# Atmega.net
KiCad netlist of a schematic drawn in EAGLE
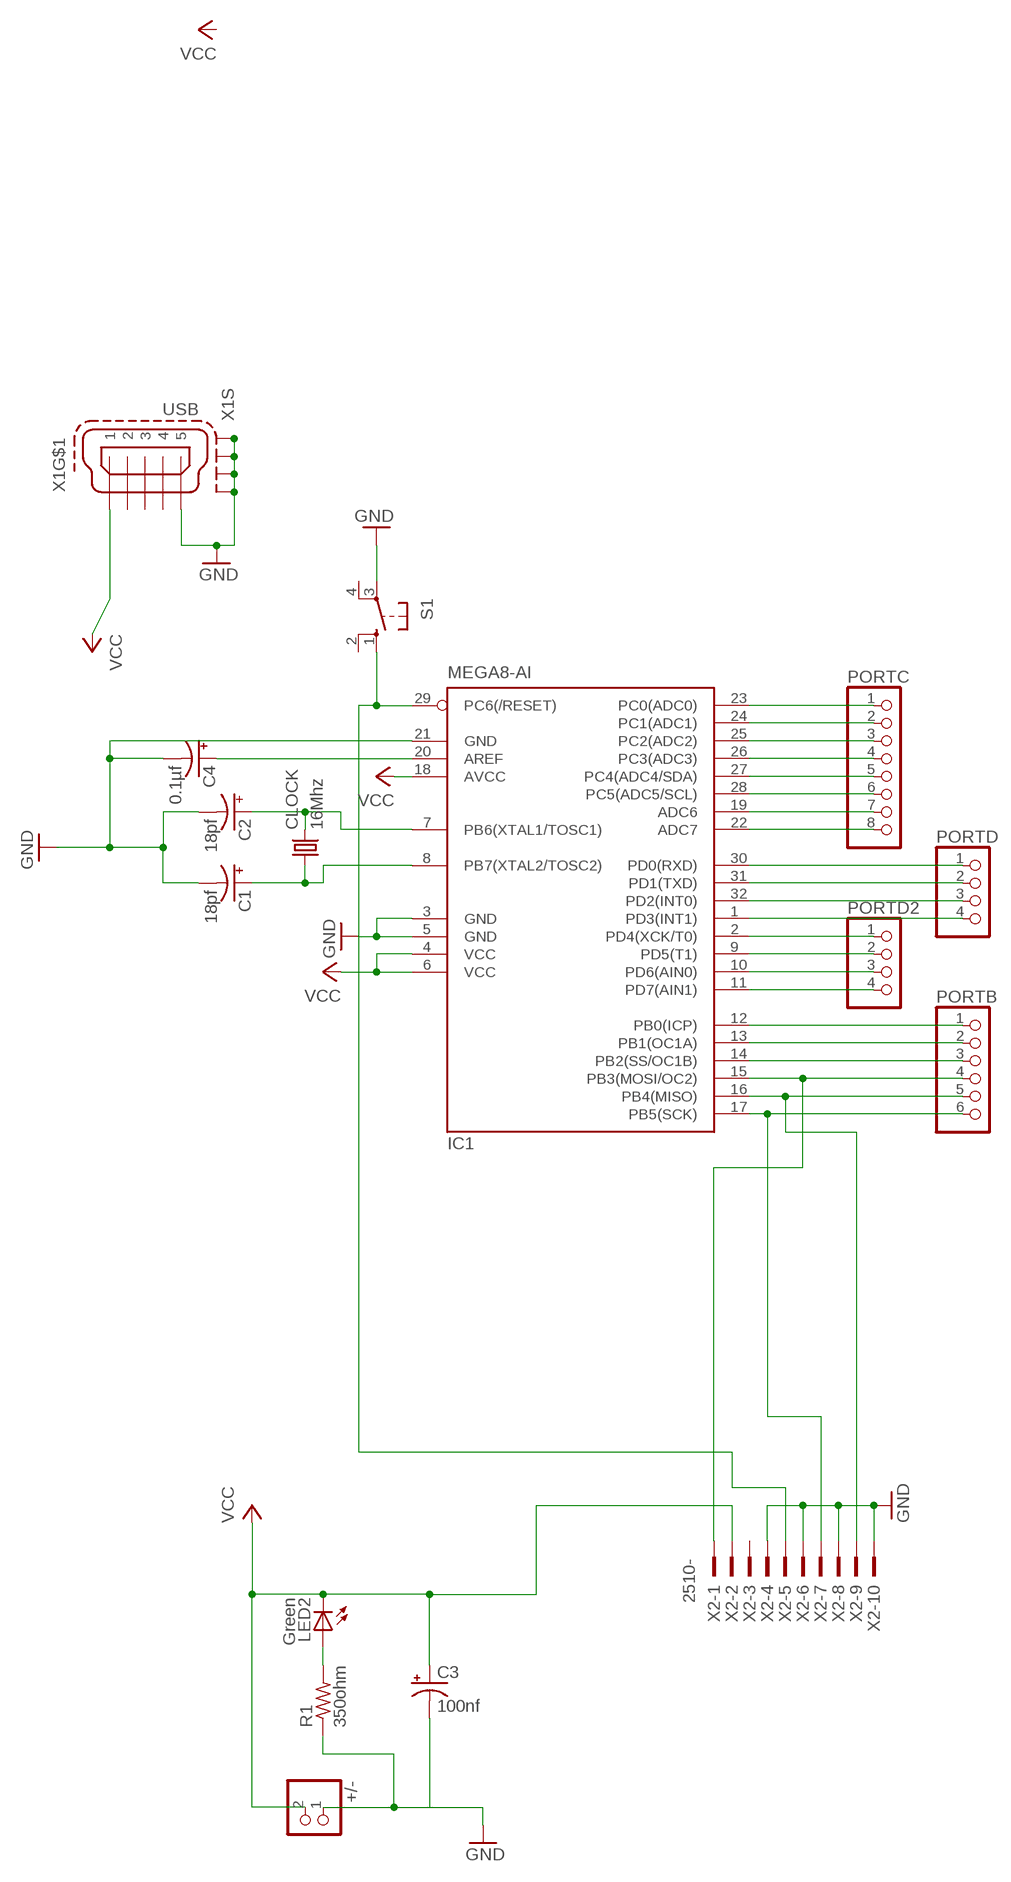
[diagram p0: schematic, sheet 1]

(export (version "E")
  (design (tool "Eeschema 10.0.6"))
  (components
    (comp (ref "+/-")
      (value "PINHD-1X2")
      (footprint "eagle-import:1X02")
      (libsource (lib "eagle-import") (part "PINHD-1X2"))
    )
    (comp (ref "C1")
      (value "18pf")
      (footprint "eagle-import:SMC_Z")
      (libsource (lib "eagle-import") (part "CPOL-USSMCZ"))
    )
    (comp (ref "C2")
      (value "18pf")
      (footprint "eagle-import:SMC_Z")
      (libsource (lib "eagle-import") (part "CPOL-USSMCZ"))
    )
    (comp (ref "C3")
      (value "100nf")
      (footprint "eagle-import:SMC_Z")
      (libsource (lib "eagle-import") (part "CPOL-USSMCZ"))
    )
    (comp (ref "C4")
      (value "0.1µf")
      (footprint "eagle-import:SMC_Z")
      (libsource (lib "eagle-import") (part "CPOL-USSMCZ"))
    )
    (comp (ref "CLOCK")
      (value "16Mhz")
      (footprint "eagle-import:HC49UP")
      (libsource (lib "eagle-import") (part "CRYSTALHC49UP"))
    )
    (comp (ref "IC1")
      (value "MEGA8-AI")
      (footprint "eagle-import:TQFP32-08")
      (fields (field (name "MPN") "ATMEGA8-16AU"))
      (libsource (lib "eagle-import") (part "MEGA8-AI"))
    )
    (comp (ref "LED2")
      (value "Green")
      (footprint "eagle-import:PLCC2")
      (fields (field (name "COLOR") "green"))
      (libsource (lib "eagle-import") (part "_T679-?-1E1F1LG"))
    )
    (comp (ref "PORTB")
      (value "PINHD-1X6")
      (footprint "eagle-import:1X06")
      (libsource (lib "eagle-import") (part "PINHD-1X6"))
    )
    (comp (ref "PORTC")
      (value "PINHD-1X8")
      (footprint "eagle-import:1X08")
      (libsource (lib "eagle-import") (part "PINHD-1X8"))
    )
    (comp (ref "PORTD")
      (value "PINHD-1X4")
      (footprint "eagle-import:1X04")
      (libsource (lib "eagle-import") (part "PINHD-1X4"))
    )
    (comp (ref "PORTD2")
      (value "PINHD-1X4")
      (footprint "eagle-import:1X04")
      (libsource (lib "eagle-import") (part "PINHD-1X4"))
    )
    (comp (ref "R1")
      (value "350ohm")
      (footprint "eagle-import:M0805")
      (libsource (lib "eagle-import") (part "R-US_M0805"))
    )
    (comp (ref "S1")
      (value "10-XX")
      (footprint "eagle-import:B3F-10XX")
      (fields (field (name "MPN") "B3F-1000"))
      (libsource (lib "eagle-import") (part "10-XX"))
    )
    (comp (ref "X1")
      (value "USB")
      (footprint "eagle-import:32005-201")
      (libsource (lib "eagle-import") (part "MINI-USB-SCHIELD-32005-201"))
    )
    (comp (ref "X2")
      (value "2510-")
      (footprint "eagle-import:PAK100_2500-10")
      (fields (field (name "MF") "3M") (field (name "MPN") "2510-6002UB"))
      (libsource (lib "eagle-import") (part "2510-"))
    )
  )
  (nets
    (net (code "1") (name "GND") (class "Default")
      (node (ref "+/-") (pin "1") (pinfunction "1_1") (pintype "passive"))
      (node (ref "C1") (pin "-") (pinfunction "-_-") (pintype "passive"))
      (node (ref "C2") (pin "-") (pinfunction "-_-") (pintype "passive"))
      (node (ref "C3") (pin "-") (pinfunction "-_-") (pintype "passive"))
      (node (ref "C4") (pin "-") (pinfunction "-_-") (pintype "passive"))
      (node (ref "IC1") (pin "21") (pinfunction "GND_21") (pintype "power_in"))
      (node (ref "IC1") (pin "3") (pinfunction "GND_3") (pintype "power_in"))
      (node (ref "IC1") (pin "5") (pinfunction "GND_5") (pintype "power_in"))
      (node (ref "R1") (pin "1") (pinfunction "1_1") (pintype "passive"))
      (node (ref "S1") (pin "3") (pinfunction "P_3") (pintype "passive"))
      (node (ref "X1") (pin "5") (pinfunction "5_5") (pintype "passive"))
      (node (ref "X1") (pin "M1") (pinfunction "S1_M1") (pintype "passive"))
      (node (ref "X1") (pin "M2") (pinfunction "S2_M2") (pintype "passive"))
      (node (ref "X1") (pin "M3") (pinfunction "S3_M3") (pintype "passive"))
      (node (ref "X1") (pin "M4") (pinfunction "S4_M4") (pintype "passive"))
      (node (ref "X2") (pin "10") (pinfunction "KL_10") (pintype "passive"))
      (node (ref "X2") (pin "4") (pinfunction "KL_4") (pintype "passive"))
      (node (ref "X2") (pin "6") (pinfunction "KL_6") (pintype "passive"))
      (node (ref "X2") (pin "8") (pinfunction "KL_8") (pintype "passive"))
    )
    (net (code "2") (name "Net-(IC1-ADC6)") (class "Default")
      (node (ref "IC1") (pin "19") (pinfunction "ADC6_19") (pintype "bidirectional"))
      (node (ref "PORTC") (pin "7") (pinfunction "7_7") (pintype "passive"))
    )
    (net (code "3") (name "Net-(IC1-ADC7)") (class "Default")
      (node (ref "IC1") (pin "22") (pinfunction "ADC7_22") (pintype "bidirectional"))
      (node (ref "PORTC") (pin "8") (pinfunction "8_8") (pintype "passive"))
    )
    (net (code "4") (name "Net-(IC1-AREF)") (class "Default")
      (node (ref "C4") (pin "+") (pinfunction "+_+") (pintype "passive"))
      (node (ref "IC1") (pin "20") (pinfunction "AREF_20") (pintype "passive"))
    )
    (net (code "5") (name "Net-(IC1-PB0(ICP))") (class "Default")
      (node (ref "IC1") (pin "12") (pinfunction "PB0(ICP)_12") (pintype "bidirectional"))
      (node (ref "PORTB") (pin "1") (pinfunction "1_1") (pintype "passive"))
    )
    (net (code "6") (name "Net-(IC1-PB1(OC1A))") (class "Default")
      (node (ref "IC1") (pin "13") (pinfunction "PB1(OC1A)_13") (pintype "bidirectional"))
      (node (ref "PORTB") (pin "2") (pinfunction "2_2") (pintype "passive"))
    )
    (net (code "7") (name "Net-(IC1-PB2(SS{slash}OC1B))") (class "Default")
      (node (ref "IC1") (pin "14") (pinfunction "PB2(SS/OC1B)_14") (pintype "bidirectional"))
      (node (ref "PORTB") (pin "3") (pinfunction "3_3") (pintype "passive"))
    )
    (net (code "8") (name "Net-(IC1-PB3(MOSI{slash}OC2))") (class "Default")
      (node (ref "IC1") (pin "15") (pinfunction "PB3(MOSI/OC2)_15") (pintype "bidirectional"))
      (node (ref "PORTB") (pin "4") (pinfunction "4_4") (pintype "passive"))
      (node (ref "X2") (pin "1") (pinfunction "KL_1") (pintype "passive"))
    )
    (net (code "9") (name "Net-(IC1-PB4(MISO))") (class "Default")
      (node (ref "IC1") (pin "16") (pinfunction "PB4(MISO)_16") (pintype "bidirectional"))
      (node (ref "PORTB") (pin "5") (pinfunction "5_5") (pintype "passive"))
      (node (ref "X2") (pin "9") (pinfunction "KL_9") (pintype "passive"))
    )
    (net (code "10") (name "Net-(IC1-PB5(SCK))") (class "Default")
      (node (ref "IC1") (pin "17") (pinfunction "PB5(SCK)_17") (pintype "bidirectional"))
      (node (ref "PORTB") (pin "6") (pinfunction "6_6") (pintype "passive"))
      (node (ref "X2") (pin "7") (pinfunction "KL_7") (pintype "passive"))
    )
    (net (code "11") (name "Net-(IC1-PB6(XTAL1{slash}TOSC1))") (class "Default")
      (node (ref "C2") (pin "+") (pinfunction "+_+") (pintype "passive"))
      (node (ref "CLOCK") (pin "2") (pinfunction "2_2") (pintype "passive"))
      (node (ref "IC1") (pin "7") (pinfunction "PB6(XTAL1/TOSC1)_7") (pintype "bidirectional"))
    )
    (net (code "12") (name "Net-(IC1-PB7(XTAL2{slash}TOSC2))") (class "Default")
      (node (ref "C1") (pin "+") (pinfunction "+_+") (pintype "passive"))
      (node (ref "CLOCK") (pin "1") (pinfunction "1_1") (pintype "passive"))
      (node (ref "IC1") (pin "8") (pinfunction "PB7(XTAL2/TOSC2)_8") (pintype "bidirectional"))
    )
    (net (code "13") (name "Net-(IC1-PC0(ADC0))") (class "Default")
      (node (ref "IC1") (pin "23") (pinfunction "PC0(ADC0)_23") (pintype "bidirectional"))
      (node (ref "PORTC") (pin "1") (pinfunction "1_1") (pintype "passive"))
    )
    (net (code "14") (name "Net-(IC1-PC1(ADC1))") (class "Default")
      (node (ref "IC1") (pin "24") (pinfunction "PC1(ADC1)_24") (pintype "bidirectional"))
      (node (ref "PORTC") (pin "2") (pinfunction "2_2") (pintype "passive"))
    )
    (net (code "15") (name "Net-(IC1-PC2(ADC2))") (class "Default")
      (node (ref "IC1") (pin "25") (pinfunction "PC2(ADC2)_25") (pintype "bidirectional"))
      (node (ref "PORTC") (pin "3") (pinfunction "3_3") (pintype "passive"))
    )
    (net (code "16") (name "Net-(IC1-PC3(ADC3))") (class "Default")
      (node (ref "IC1") (pin "26") (pinfunction "PC3(ADC3)_26") (pintype "bidirectional"))
      (node (ref "PORTC") (pin "4") (pinfunction "4_4") (pintype "passive"))
    )
    (net (code "17") (name "Net-(IC1-PC4(ADC4{slash}SDA))") (class "Default")
      (node (ref "IC1") (pin "27") (pinfunction "PC4(ADC4/SDA)_27") (pintype "bidirectional"))
      (node (ref "PORTC") (pin "5") (pinfunction "5_5") (pintype "passive"))
    )
    (net (code "18") (name "Net-(IC1-PC5(ADC5{slash}SCL))") (class "Default")
      (node (ref "IC1") (pin "28") (pinfunction "PC5(ADC5/SCL)_28") (pintype "bidirectional"))
      (node (ref "PORTC") (pin "6") (pinfunction "6_6") (pintype "passive"))
    )
    (net (code "19") (name "Net-(IC1-PC6({slash}RESET))") (class "Default")
      (node (ref "IC1") (pin "29") (pinfunction "PC6(/RESET)_29") (pintype "bidirectional"))
      (node (ref "S1") (pin "1") (pinfunction "S_1") (pintype "passive"))
      (node (ref "X2") (pin "5") (pinfunction "KL_5") (pintype "passive"))
    )
    (net (code "20") (name "Net-(IC1-PD0(RXD))") (class "Default")
      (node (ref "IC1") (pin "30") (pinfunction "PD0(RXD)_30") (pintype "bidirectional"))
      (node (ref "PORTD") (pin "1") (pinfunction "1_1") (pintype "passive"))
    )
    (net (code "21") (name "Net-(IC1-PD1(TXD))") (class "Default")
      (node (ref "IC1") (pin "31") (pinfunction "PD1(TXD)_31") (pintype "bidirectional"))
      (node (ref "PORTD") (pin "2") (pinfunction "2_2") (pintype "passive"))
    )
    (net (code "22") (name "Net-(IC1-PD2(INT0))") (class "Default")
      (node (ref "IC1") (pin "32") (pinfunction "PD2(INT0)_32") (pintype "bidirectional"))
      (node (ref "PORTD") (pin "3") (pinfunction "3_3") (pintype "passive"))
    )
    (net (code "23") (name "Net-(IC1-PD3(INT1))") (class "Default")
      (node (ref "IC1") (pin "1") (pinfunction "PD3(INT1)_1") (pintype "bidirectional"))
      (node (ref "PORTD") (pin "4") (pinfunction "4_4") (pintype "passive"))
    )
    (net (code "24") (name "Net-(IC1-PD4(XCK{slash}T0))") (class "Default")
      (node (ref "IC1") (pin "2") (pinfunction "PD4(XCK/T0)_2") (pintype "bidirectional"))
      (node (ref "PORTD2") (pin "1") (pinfunction "1_1") (pintype "passive"))
    )
    (net (code "25") (name "Net-(IC1-PD5(T1))") (class "Default")
      (node (ref "IC1") (pin "9") (pinfunction "PD5(T1)_9") (pintype "bidirectional"))
      (node (ref "PORTD2") (pin "2") (pinfunction "2_2") (pintype "passive"))
    )
    (net (code "26") (name "Net-(IC1-PD6(AIN0))") (class "Default")
      (node (ref "IC1") (pin "10") (pinfunction "PD6(AIN0)_10") (pintype "bidirectional"))
      (node (ref "PORTD2") (pin "3") (pinfunction "3_3") (pintype "passive"))
    )
    (net (code "27") (name "Net-(IC1-PD7(AIN1))") (class "Default")
      (node (ref "IC1") (pin "11") (pinfunction "PD7(AIN1)_11") (pintype "bidirectional"))
      (node (ref "PORTD2") (pin "4") (pinfunction "4_4") (pintype "passive"))
    )
    (net (code "28") (name "Net-(LED2-PadA)") (class "Default")
      (node (ref "LED2") (pin "A") (pinfunction "A_A") (pintype "passive"))
      (node (ref "R1") (pin "2") (pinfunction "2_2") (pintype "passive"))
    )
    (net (code "29") (name "VCC") (class "Default")
      (node (ref "+/-") (pin "2") (pinfunction "2_2") (pintype "passive"))
      (node (ref "C3") (pin "+") (pinfunction "+_+") (pintype "passive"))
      (node (ref "IC1") (pin "18") (pinfunction "AVCC_18") (pintype "power_in"))
      (node (ref "IC1") (pin "4") (pinfunction "VCC_4") (pintype "power_in"))
      (node (ref "IC1") (pin "6") (pinfunction "VCC_6") (pintype "power_in"))
      (node (ref "LED2") (pin "C") (pinfunction "C_C") (pintype "passive"))
      (node (ref "X1") (pin "1") (pinfunction "1_1") (pintype "passive"))
      (node (ref "X2") (pin "2") (pinfunction "KL_2") (pintype "passive"))
    )
    (net (code "30") (name "unconnected-(S1-P1-Pad4)") (class "Default")
      (node (ref "S1") (pin "4") (pinfunction "P1_4") (pintype "passive"))
    )
    (net (code "31") (name "unconnected-(S1-S1-Pad2)") (class "Default")
      (node (ref "S1") (pin "2") (pinfunction "S1_2") (pintype "passive"))
    )
    (net (code "32") (name "unconnected-(X1-Pad2)") (class "Default")
      (node (ref "X1") (pin "2") (pinfunction "2_2") (pintype "passive"))
    )
    (net (code "33") (name "unconnected-(X1-Pad3)") (class "Default")
      (node (ref "X1") (pin "3") (pinfunction "3_3") (pintype "passive"))
    )
    (net (code "34") (name "unconnected-(X1-Pad4)") (class "Default")
      (node (ref "X1") (pin "4") (pinfunction "4_4") (pintype "passive"))
    )
    (net (code "35") (name "unconnected-(X2D-KL-Pad3)") (class "Default")
      (node (ref "X2") (pin "3") (pinfunction "KL_3") (pintype "passive"))
    )
  )
)
